# axocore_top_from_mech.net
KiCad netlist of a schematic drawn in EAGLE
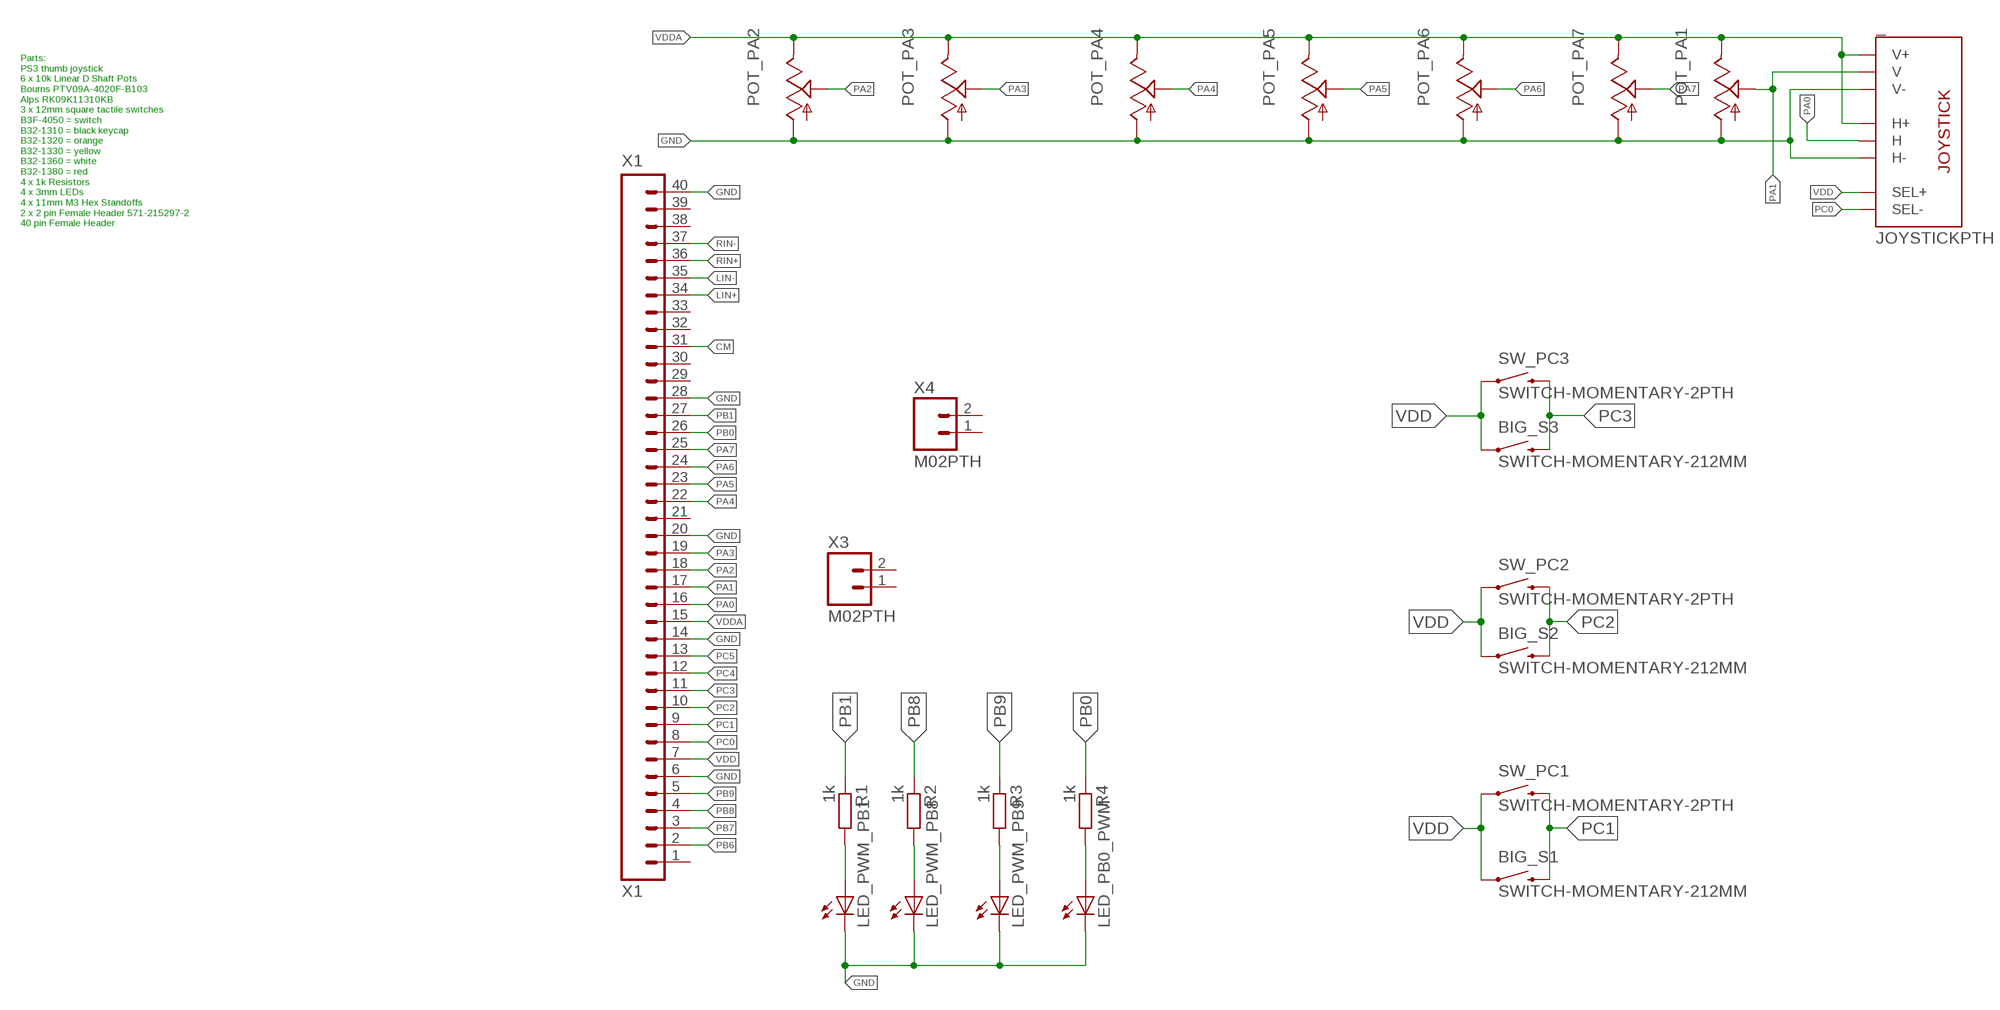
[diagram p0: schematic, sheet 1]

(export (version "E")
  (design (tool "Eeschema 10.0.6"))
  (components
    (comp (ref "BIG_S1")
      (value "SWITCH-MOMENTARY-212MM")
      (footprint "eagle-import:TACTILE-PTH-12MM")
      (libsource (lib "eagle-import") (part "SWITCH-MOMENTARY-212MM"))
    )
    (comp (ref "BIG_S2")
      (value "SWITCH-MOMENTARY-212MM")
      (footprint "eagle-import:TACTILE-PTH-12MM")
      (libsource (lib "eagle-import") (part "SWITCH-MOMENTARY-212MM"))
    )
    (comp (ref "BIG_S3")
      (value "SWITCH-MOMENTARY-212MM")
      (footprint "eagle-import:TACTILE-PTH-12MM")
      (libsource (lib "eagle-import") (part "SWITCH-MOMENTARY-212MM"))
    )
    (comp (ref "LED_PB0_PWM")
      (value "LED3MM")
      (footprint "eagle-import:LED3MM")
      (libsource (lib "eagle-import") (part "LED3MM"))
    )
    (comp (ref "LED_PWM_PB1")
      (value "LED3MM")
      (footprint "eagle-import:LED3MM")
      (libsource (lib "eagle-import") (part "LED3MM"))
    )
    (comp (ref "LED_PWM_PB8")
      (value "LED3MM")
      (footprint "eagle-import:LED3MM")
      (libsource (lib "eagle-import") (part "LED3MM"))
    )
    (comp (ref "LED_PWM_PB9")
      (value "LED3MM")
      (footprint "eagle-import:LED3MM")
      (libsource (lib "eagle-import") (part "LED3MM"))
    )
    (comp (ref "POT_PA1")
      (value "9MM_SNAP-IN_POT_")
      (footprint "eagle-import:9MM_SNAP-IN_POT")
      (libsource (lib "eagle-import") (part "9MM_SNAP-IN_POT_"))
    )
    (comp (ref "POT_PA2")
      (value "9MM_SNAP-IN_POT_")
      (footprint "eagle-import:9MM_SNAP-IN_POT")
      (libsource (lib "eagle-import") (part "9MM_SNAP-IN_POT_"))
    )
    (comp (ref "POT_PA3")
      (value "9MM_SNAP-IN_POT_")
      (footprint "eagle-import:9MM_SNAP-IN_POT")
      (libsource (lib "eagle-import") (part "9MM_SNAP-IN_POT_"))
    )
    (comp (ref "POT_PA4")
      (value "9MM_SNAP-IN_POT_")
      (footprint "eagle-import:9MM_SNAP-IN_POT")
      (libsource (lib "eagle-import") (part "9MM_SNAP-IN_POT_"))
    )
    (comp (ref "POT_PA5")
      (value "9MM_SNAP-IN_POT_")
      (footprint "eagle-import:9MM_SNAP-IN_POT")
      (libsource (lib "eagle-import") (part "9MM_SNAP-IN_POT_"))
    )
    (comp (ref "POT_PA6")
      (value "9MM_SNAP-IN_POT_")
      (footprint "eagle-import:9MM_SNAP-IN_POT")
      (libsource (lib "eagle-import") (part "9MM_SNAP-IN_POT_"))
    )
    (comp (ref "POT_PA7")
      (value "9MM_SNAP-IN_POT_")
      (footprint "eagle-import:9MM_SNAP-IN_POT")
      (libsource (lib "eagle-import") (part "9MM_SNAP-IN_POT_"))
    )
    (comp (ref "R1")
      (value "1k")
      (footprint "eagle-import:7MM_RESISTOR")
      (libsource (lib "eagle-import") (part "RESISTOR7MM"))
    )
    (comp (ref "R2")
      (value "1k")
      (footprint "eagle-import:7MM_RESISTOR")
      (libsource (lib "eagle-import") (part "RESISTOR7MM"))
    )
    (comp (ref "R3")
      (value "1k")
      (footprint "eagle-import:7MM_RESISTOR")
      (libsource (lib "eagle-import") (part "RESISTOR7MM"))
    )
    (comp (ref "R4")
      (value "1k")
      (footprint "eagle-import:7MM_RESISTOR")
      (libsource (lib "eagle-import") (part "RESISTOR7MM"))
    )
    (comp (ref "SW_PC1")
      (value "SWITCH-MOMENTARY-2PTH")
      (footprint "eagle-import:TACTILE-PTH")
      (libsource (lib "eagle-import") (part "SWITCH-MOMENTARY-2PTH"))
    )
    (comp (ref "SW_PC2")
      (value "SWITCH-MOMENTARY-2PTH")
      (footprint "eagle-import:TACTILE-PTH")
      (libsource (lib "eagle-import") (part "SWITCH-MOMENTARY-2PTH"))
    )
    (comp (ref "SW_PC3")
      (value "SWITCH-MOMENTARY-2PTH")
      (footprint "eagle-import:TACTILE-PTH")
      (libsource (lib "eagle-import") (part "SWITCH-MOMENTARY-2PTH"))
    )
    (comp (ref "X1")
      (value "X1")
      (footprint "eagle-import:1X40")
      (libsource (lib "eagle-import") (part "M40"))
    )
    (comp (ref "X3")
      (value "M02PTH")
      (footprint "eagle-import:1X02")
      (libsource (lib "eagle-import") (part "M02PTH"))
    )
    (comp (ref "X4")
      (value "M02PTH")
      (footprint "eagle-import:1X02")
      (libsource (lib "eagle-import") (part "M02PTH"))
    )
    (comp (ref "_")
      (value "JOYSTICKPTH")
      (footprint "eagle-import:JOYSTICK")
      (libsource (lib "eagle-import") (part "JOYSTICKPTH"))
    )
  )
  (nets
    (net (code "1") (name "CM") (class "Default")
      (node (ref "X1") (pin "31") (pinfunction "31_31") (pintype "passive"))
    )
    (net (code "2") (name "GND") (class "Default")
      (node (ref "LED_PB0_PWM") (pin "K") (pinfunction "C_K") (pintype "passive"))
      (node (ref "LED_PWM_PB1") (pin "K") (pinfunction "C_K") (pintype "passive"))
      (node (ref "LED_PWM_PB8") (pin "K") (pinfunction "C_K") (pintype "passive"))
      (node (ref "LED_PWM_PB9") (pin "K") (pinfunction "C_K") (pintype "passive"))
      (node (ref "POT_PA1") (pin "1") (pinfunction "A_1") (pintype "passive"))
      (node (ref "POT_PA2") (pin "1") (pinfunction "A_1") (pintype "passive"))
      (node (ref "POT_PA3") (pin "1") (pinfunction "A_1") (pintype "passive"))
      (node (ref "POT_PA4") (pin "1") (pinfunction "A_1") (pintype "passive"))
      (node (ref "POT_PA5") (pin "1") (pinfunction "A_1") (pintype "passive"))
      (node (ref "POT_PA6") (pin "1") (pinfunction "A_1") (pintype "passive"))
      (node (ref "POT_PA7") (pin "1") (pinfunction "A_1") (pintype "passive"))
      (node (ref "X1") (pin "14") (pinfunction "14_14") (pintype "passive"))
      (node (ref "X1") (pin "20") (pinfunction "20_20") (pintype "passive"))
      (node (ref "X1") (pin "28") (pinfunction "28_28") (pintype "passive"))
      (node (ref "X1") (pin "40") (pinfunction "40_40") (pintype "passive"))
      (node (ref "X1") (pin "6") (pinfunction "6_6") (pintype "passive"))
      (node (ref "_") (pin "H3") (pinfunction "H-_H3") (pintype "bidirectional"))
      (node (ref "_") (pin "V3") (pinfunction "V-_V3") (pintype "bidirectional"))
    )
    (net (code "3") (name "LIN+") (class "Default")
      (node (ref "X1") (pin "34") (pinfunction "34_34") (pintype "passive"))
    )
    (net (code "4") (name "LIN-") (class "Default")
      (node (ref "X1") (pin "35") (pinfunction "35_35") (pintype "passive"))
    )
    (net (code "5") (name "Net-(LED_PB0_PWM-PadA)") (class "Default")
      (node (ref "LED_PB0_PWM") (pin "A") (pinfunction "A_A") (pintype "passive"))
      (node (ref "R4") (pin "2") (pinfunction "2_2") (pintype "passive"))
    )
    (net (code "6") (name "Net-(LED_PWM_PB1-PadA)") (class "Default")
      (node (ref "LED_PWM_PB1") (pin "A") (pinfunction "A_A") (pintype "passive"))
      (node (ref "R1") (pin "2") (pinfunction "2_2") (pintype "passive"))
    )
    (net (code "7") (name "Net-(LED_PWM_PB8-PadA)") (class "Default")
      (node (ref "LED_PWM_PB8") (pin "A") (pinfunction "A_A") (pintype "passive"))
      (node (ref "R2") (pin "2") (pinfunction "2_2") (pintype "passive"))
    )
    (net (code "8") (name "Net-(LED_PWM_PB9-PadA)") (class "Default")
      (node (ref "LED_PWM_PB9") (pin "A") (pinfunction "A_A") (pintype "passive"))
      (node (ref "R3") (pin "2") (pinfunction "2_2") (pintype "passive"))
    )
    (net (code "9") (name "PA0") (class "Default")
      (node (ref "X1") (pin "16") (pinfunction "16_16") (pintype "passive"))
      (node (ref "_") (pin "H2") (pinfunction "H_H2") (pintype "bidirectional"))
    )
    (net (code "10") (name "PA1") (class "Default")
      (node (ref "POT_PA1") (pin "2") (pinfunction "S_2") (pintype "passive"))
      (node (ref "X1") (pin "17") (pinfunction "17_17") (pintype "passive"))
      (node (ref "_") (pin "V2") (pinfunction "V_V2") (pintype "bidirectional"))
    )
    (net (code "11") (name "PA2") (class "Default")
      (node (ref "POT_PA2") (pin "2") (pinfunction "S_2") (pintype "passive"))
      (node (ref "X1") (pin "18") (pinfunction "18_18") (pintype "passive"))
    )
    (net (code "12") (name "PA3") (class "Default")
      (node (ref "POT_PA3") (pin "2") (pinfunction "S_2") (pintype "passive"))
      (node (ref "X1") (pin "19") (pinfunction "19_19") (pintype "passive"))
    )
    (net (code "13") (name "PA4") (class "Default")
      (node (ref "POT_PA4") (pin "2") (pinfunction "S_2") (pintype "passive"))
      (node (ref "X1") (pin "22") (pinfunction "22_22") (pintype "passive"))
    )
    (net (code "14") (name "PA5") (class "Default")
      (node (ref "POT_PA5") (pin "2") (pinfunction "S_2") (pintype "passive"))
      (node (ref "X1") (pin "23") (pinfunction "23_23") (pintype "passive"))
    )
    (net (code "15") (name "PA6") (class "Default")
      (node (ref "POT_PA6") (pin "2") (pinfunction "S_2") (pintype "passive"))
      (node (ref "X1") (pin "24") (pinfunction "24_24") (pintype "passive"))
    )
    (net (code "16") (name "PA7") (class "Default")
      (node (ref "POT_PA7") (pin "2") (pinfunction "S_2") (pintype "passive"))
      (node (ref "X1") (pin "25") (pinfunction "25_25") (pintype "passive"))
    )
    (net (code "17") (name "PB0") (class "Default")
      (node (ref "R4") (pin "1") (pinfunction "1_1") (pintype "passive"))
      (node (ref "X1") (pin "26") (pinfunction "26_26") (pintype "passive"))
    )
    (net (code "18") (name "PB1") (class "Default")
      (node (ref "R1") (pin "1") (pinfunction "1_1") (pintype "passive"))
      (node (ref "X1") (pin "27") (pinfunction "27_27") (pintype "passive"))
    )
    (net (code "19") (name "PB6") (class "Default")
      (node (ref "X1") (pin "2") (pinfunction "2_2") (pintype "passive"))
    )
    (net (code "20") (name "PB7") (class "Default")
      (node (ref "X1") (pin "3") (pinfunction "3_3") (pintype "passive"))
    )
    (net (code "21") (name "PB8") (class "Default")
      (node (ref "R2") (pin "1") (pinfunction "1_1") (pintype "passive"))
      (node (ref "X1") (pin "4") (pinfunction "4_4") (pintype "passive"))
    )
    (net (code "22") (name "PB9") (class "Default")
      (node (ref "R3") (pin "1") (pinfunction "1_1") (pintype "passive"))
      (node (ref "X1") (pin "5") (pinfunction "5_5") (pintype "passive"))
    )
    (net (code "23") (name "PC0") (class "Default")
      (node (ref "X1") (pin "8") (pinfunction "8_8") (pintype "passive"))
      (node (ref "_") (pin "B2A") (pinfunction "SEL-_B2A") (pintype "bidirectional"))
    )
    (net (code "24") (name "PC1") (class "Default")
      (node (ref "BIG_S1") (pin "3") (pinfunction "2_3") (pintype "passive"))
      (node (ref "SW_PC1") (pin "3") (pinfunction "2_3") (pintype "passive"))
      (node (ref "X1") (pin "9") (pinfunction "9_9") (pintype "passive"))
    )
    (net (code "25") (name "PC2") (class "Default")
      (node (ref "BIG_S2") (pin "3") (pinfunction "2_3") (pintype "passive"))
      (node (ref "SW_PC2") (pin "3") (pinfunction "2_3") (pintype "passive"))
      (node (ref "X1") (pin "10") (pinfunction "10_10") (pintype "passive"))
    )
    (net (code "26") (name "PC3") (class "Default")
      (node (ref "BIG_S3") (pin "3") (pinfunction "2_3") (pintype "passive"))
      (node (ref "SW_PC3") (pin "3") (pinfunction "2_3") (pintype "passive"))
      (node (ref "X1") (pin "11") (pinfunction "11_11") (pintype "passive"))
    )
    (net (code "27") (name "PC4") (class "Default")
      (node (ref "X1") (pin "12") (pinfunction "12_12") (pintype "passive"))
    )
    (net (code "28") (name "PC5") (class "Default")
      (node (ref "X1") (pin "13") (pinfunction "13_13") (pintype "passive"))
    )
    (net (code "29") (name "RIN+") (class "Default")
      (node (ref "X1") (pin "36") (pinfunction "36_36") (pintype "passive"))
    )
    (net (code "30") (name "RIN-") (class "Default")
      (node (ref "X1") (pin "37") (pinfunction "37_37") (pintype "passive"))
    )
    (net (code "31") (name "VDD") (class "Default")
      (node (ref "BIG_S1") (pin "1") (pinfunction "1_1") (pintype "passive"))
      (node (ref "BIG_S2") (pin "1") (pinfunction "1_1") (pintype "passive"))
      (node (ref "BIG_S3") (pin "1") (pinfunction "1_1") (pintype "passive"))
      (node (ref "SW_PC1") (pin "1") (pinfunction "1_1") (pintype "passive"))
      (node (ref "SW_PC2") (pin "1") (pinfunction "1_1") (pintype "passive"))
      (node (ref "SW_PC3") (pin "1") (pinfunction "1_1") (pintype "passive"))
      (node (ref "X1") (pin "7") (pinfunction "7_7") (pintype "passive"))
      (node (ref "_") (pin "B1A") (pinfunction "SEL+_B1A") (pintype "bidirectional"))
    )
    (net (code "32") (name "VDDA") (class "Default")
      (node (ref "POT_PA1") (pin "3") (pinfunction "E_3") (pintype "passive"))
      (node (ref "POT_PA2") (pin "3") (pinfunction "E_3") (pintype "passive"))
      (node (ref "POT_PA3") (pin "3") (pinfunction "E_3") (pintype "passive"))
      (node (ref "POT_PA4") (pin "3") (pinfunction "E_3") (pintype "passive"))
      (node (ref "POT_PA5") (pin "3") (pinfunction "E_3") (pintype "passive"))
      (node (ref "POT_PA6") (pin "3") (pinfunction "E_3") (pintype "passive"))
      (node (ref "POT_PA7") (pin "3") (pinfunction "E_3") (pintype "passive"))
      (node (ref "X1") (pin "15") (pinfunction "15_15") (pintype "passive"))
      (node (ref "_") (pin "H1") (pinfunction "H+_H1") (pintype "bidirectional"))
      (node (ref "_") (pin "V1") (pinfunction "V+_V1") (pintype "bidirectional"))
    )
    (net (code "33") (name "unconnected-(X1-Pad1)") (class "Default")
      (node (ref "X1") (pin "1") (pinfunction "1_1") (pintype "passive"))
    )
    (net (code "34") (name "unconnected-(X1-Pad21)") (class "Default")
      (node (ref "X1") (pin "21") (pinfunction "21_21") (pintype "passive"))
    )
    (net (code "35") (name "unconnected-(X1-Pad29)") (class "Default")
      (node (ref "X1") (pin "29") (pinfunction "29_29") (pintype "passive"))
    )
    (net (code "36") (name "unconnected-(X1-Pad30)") (class "Default")
      (node (ref "X1") (pin "30") (pinfunction "30_30") (pintype "passive"))
    )
    (net (code "37") (name "unconnected-(X1-Pad32)") (class "Default")
      (node (ref "X1") (pin "32") (pinfunction "32_32") (pintype "passive"))
    )
    (net (code "38") (name "unconnected-(X1-Pad33)") (class "Default")
      (node (ref "X1") (pin "33") (pinfunction "33_33") (pintype "passive"))
    )
    (net (code "39") (name "unconnected-(X1-Pad38)") (class "Default")
      (node (ref "X1") (pin "38") (pinfunction "38_38") (pintype "passive"))
    )
    (net (code "40") (name "unconnected-(X1-Pad39)") (class "Default")
      (node (ref "X1") (pin "39") (pinfunction "39_39") (pintype "passive"))
    )
    (net (code "41") (name "unconnected-(X3-Pad1)") (class "Default")
      (node (ref "X3") (pin "1") (pinfunction "1_1") (pintype "passive"))
    )
    (net (code "42") (name "unconnected-(X3-Pad2)") (class "Default")
      (node (ref "X3") (pin "2") (pinfunction "2_2") (pintype "passive"))
    )
    (net (code "43") (name "unconnected-(X4-Pad1)") (class "Default")
      (node (ref "X4") (pin "1") (pinfunction "1_1") (pintype "passive"))
    )
    (net (code "44") (name "unconnected-(X4-Pad2)") (class "Default")
      (node (ref "X4") (pin "2") (pinfunction "2_2") (pintype "passive"))
    )
  )
)
